# COUNTER.net
KiCad netlist of a schematic drawn in EAGLE
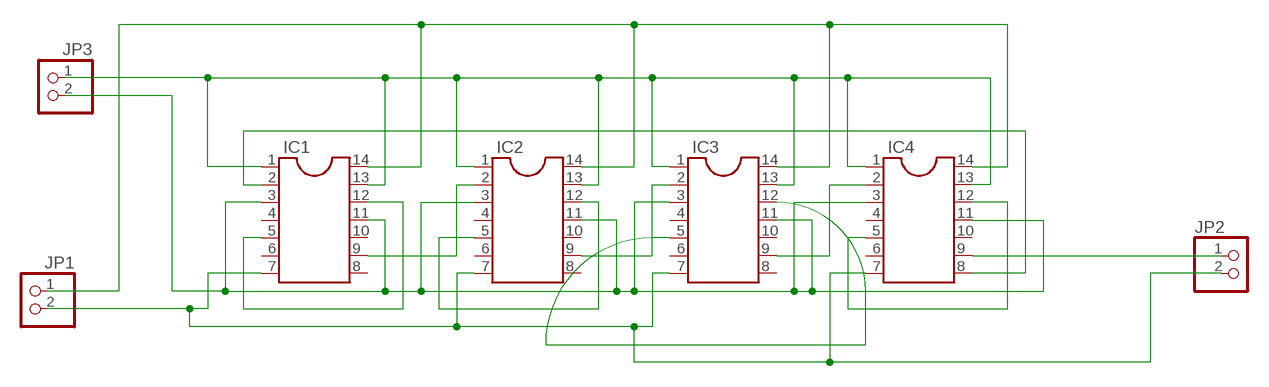
[diagram p0: schematic, sheet 1]

(export (version "E")
  (design (tool "Eeschema 10.0.6"))
  (components
    (comp (ref "IC1")
      (value "DIL14")
      (footprint "eagle-import:DIL14")
      (libsource (lib "eagle-import") (part "DIL14"))
    )
    (comp (ref "IC2")
      (value "DIL14")
      (footprint "eagle-import:DIL14")
      (libsource (lib "eagle-import") (part "DIL14"))
    )
    (comp (ref "IC3")
      (value "DIL14")
      (footprint "eagle-import:DIL14")
      (libsource (lib "eagle-import") (part "DIL14"))
    )
    (comp (ref "IC4")
      (value "DIL14")
      (footprint "eagle-import:DIL14")
      (libsource (lib "eagle-import") (part "DIL14"))
    )
    (comp (ref "JP1")
      (value "PINHD-1X2")
      (footprint "eagle-import:1X02")
      (libsource (lib "eagle-import") (part "PINHD-1X2"))
    )
    (comp (ref "JP2")
      (value "PINHD-1X2")
      (footprint "eagle-import:1X02")
      (libsource (lib "eagle-import") (part "PINHD-1X2"))
    )
    (comp (ref "JP3")
      (value "PINHD-1X2")
      (footprint "eagle-import:1X02")
      (libsource (lib "eagle-import") (part "PINHD-1X2"))
    )
  )
  (nets
    (net (code "1") (name "Net-(IC1-Pad1)") (class "Default")
      (node (ref "IC1") (pin "1") (pinfunction "1_1") (pintype "passive"))
      (node (ref "IC1") (pin "13") (pinfunction "13_13") (pintype "passive"))
      (node (ref "IC2") (pin "1") (pinfunction "1_1") (pintype "passive"))
      (node (ref "IC2") (pin "13") (pinfunction "13_13") (pintype "passive"))
      (node (ref "IC3") (pin "1") (pinfunction "1_1") (pintype "passive"))
      (node (ref "IC3") (pin "13") (pinfunction "13_13") (pintype "passive"))
      (node (ref "IC4") (pin "1") (pinfunction "1_1") (pintype "passive"))
      (node (ref "IC4") (pin "13") (pinfunction "13_13") (pintype "passive"))
      (node (ref "JP3") (pin "1") (pinfunction "1_1") (pintype "passive"))
    )
    (net (code "2") (name "Net-(IC1-Pad2)") (class "Default")
      (node (ref "IC1") (pin "2") (pinfunction "2_2") (pintype "passive"))
      (node (ref "IC4") (pin "8") (pinfunction "8_8") (pintype "passive"))
    )
    (net (code "3") (name "Net-(IC1-Pad7)") (class "Default")
      (node (ref "IC1") (pin "7") (pinfunction "7_7") (pintype "passive"))
      (node (ref "IC2") (pin "7") (pinfunction "7_7") (pintype "passive"))
      (node (ref "IC3") (pin "7") (pinfunction "7_7") (pintype "passive"))
      (node (ref "IC4") (pin "7") (pinfunction "7_7") (pintype "passive"))
      (node (ref "JP1") (pin "2") (pinfunction "2_2") (pintype "passive"))
      (node (ref "JP2") (pin "2") (pinfunction "2_2") (pintype "passive"))
    )
    (net (code "4") (name "Net-(IC1-Pad9)") (class "Default")
      (node (ref "IC1") (pin "9") (pinfunction "9_9") (pintype "passive"))
      (node (ref "IC2") (pin "2") (pinfunction "2_2") (pintype "passive"))
    )
    (net (code "5") (name "Net-(IC1-Pad11)") (class "Default")
      (node (ref "IC1") (pin "11") (pinfunction "11_11") (pintype "passive"))
      (node (ref "IC1") (pin "3") (pinfunction "3_3") (pintype "passive"))
      (node (ref "IC2") (pin "11") (pinfunction "11_11") (pintype "passive"))
      (node (ref "IC2") (pin "3") (pinfunction "3_3") (pintype "passive"))
      (node (ref "IC3") (pin "11") (pinfunction "11_11") (pintype "passive"))
      (node (ref "IC3") (pin "3") (pinfunction "3_3") (pintype "passive"))
      (node (ref "IC4") (pin "11") (pinfunction "11_11") (pintype "passive"))
      (node (ref "IC4") (pin "3") (pinfunction "3_3") (pintype "passive"))
      (node (ref "JP3") (pin "2") (pinfunction "2_2") (pintype "passive"))
    )
    (net (code "6") (name "Net-(IC1-Pad12)") (class "Default")
      (node (ref "IC1") (pin "12") (pinfunction "12_12") (pintype "passive"))
      (node (ref "IC1") (pin "5") (pinfunction "5_5") (pintype "passive"))
    )
    (net (code "7") (name "Net-(IC1-Pad14)") (class "Default")
      (node (ref "IC1") (pin "14") (pinfunction "14_14") (pintype "passive"))
      (node (ref "IC2") (pin "14") (pinfunction "14_14") (pintype "passive"))
      (node (ref "IC3") (pin "14") (pinfunction "14_14") (pintype "passive"))
      (node (ref "IC4") (pin "14") (pinfunction "14_14") (pintype "passive"))
      (node (ref "JP1") (pin "1") (pinfunction "1_1") (pintype "passive"))
    )
    (net (code "8") (name "Net-(IC2-Pad9)") (class "Default")
      (node (ref "IC2") (pin "9") (pinfunction "9_9") (pintype "passive"))
      (node (ref "IC3") (pin "2") (pinfunction "2_2") (pintype "passive"))
    )
    (net (code "9") (name "Net-(IC2-Pad12)") (class "Default")
      (node (ref "IC2") (pin "12") (pinfunction "12_12") (pintype "passive"))
      (node (ref "IC2") (pin "5") (pinfunction "5_5") (pintype "passive"))
    )
    (net (code "10") (name "Net-(IC3-Pad9)") (class "Default")
      (node (ref "IC3") (pin "9") (pinfunction "9_9") (pintype "passive"))
      (node (ref "IC4") (pin "2") (pinfunction "2_2") (pintype "passive"))
    )
    (net (code "11") (name "Net-(IC3-Pad12)") (class "Default")
      (node (ref "IC3") (pin "12") (pinfunction "12_12") (pintype "passive"))
      (node (ref "IC3") (pin "5") (pinfunction "5_5") (pintype "passive"))
    )
    (net (code "12") (name "Net-(IC4-Pad9)") (class "Default")
      (node (ref "IC4") (pin "9") (pinfunction "9_9") (pintype "passive"))
      (node (ref "JP2") (pin "1") (pinfunction "1_1") (pintype "passive"))
    )
    (net (code "13") (name "Net-(IC4-Pad12)") (class "Default")
      (node (ref "IC4") (pin "12") (pinfunction "12_12") (pintype "passive"))
      (node (ref "IC4") (pin "5") (pinfunction "5_5") (pintype "passive"))
    )
    (net (code "14") (name "unconnected-(IC1-Pad4)") (class "Default")
      (node (ref "IC1") (pin "4") (pinfunction "4_4") (pintype "passive"))
    )
    (net (code "15") (name "unconnected-(IC1-Pad6)") (class "Default")
      (node (ref "IC1") (pin "6") (pinfunction "6_6") (pintype "passive"))
    )
    (net (code "16") (name "unconnected-(IC1-Pad8)") (class "Default")
      (node (ref "IC1") (pin "8") (pinfunction "8_8") (pintype "passive"))
    )
    (net (code "17") (name "unconnected-(IC1-Pad10)") (class "Default")
      (node (ref "IC1") (pin "10") (pinfunction "10_10") (pintype "passive"))
    )
    (net (code "18") (name "unconnected-(IC2-Pad4)") (class "Default")
      (node (ref "IC2") (pin "4") (pinfunction "4_4") (pintype "passive"))
    )
    (net (code "19") (name "unconnected-(IC2-Pad6)") (class "Default")
      (node (ref "IC2") (pin "6") (pinfunction "6_6") (pintype "passive"))
    )
    (net (code "20") (name "unconnected-(IC2-Pad8)") (class "Default")
      (node (ref "IC2") (pin "8") (pinfunction "8_8") (pintype "passive"))
    )
    (net (code "21") (name "unconnected-(IC2-Pad10)") (class "Default")
      (node (ref "IC2") (pin "10") (pinfunction "10_10") (pintype "passive"))
    )
    (net (code "22") (name "unconnected-(IC3-Pad4)") (class "Default")
      (node (ref "IC3") (pin "4") (pinfunction "4_4") (pintype "passive"))
    )
    (net (code "23") (name "unconnected-(IC3-Pad6)") (class "Default")
      (node (ref "IC3") (pin "6") (pinfunction "6_6") (pintype "passive"))
    )
    (net (code "24") (name "unconnected-(IC3-Pad8)") (class "Default")
      (node (ref "IC3") (pin "8") (pinfunction "8_8") (pintype "passive"))
    )
    (net (code "25") (name "unconnected-(IC3-Pad10)") (class "Default")
      (node (ref "IC3") (pin "10") (pinfunction "10_10") (pintype "passive"))
    )
    (net (code "26") (name "unconnected-(IC4-Pad4)") (class "Default")
      (node (ref "IC4") (pin "4") (pinfunction "4_4") (pintype "passive"))
    )
    (net (code "27") (name "unconnected-(IC4-Pad6)") (class "Default")
      (node (ref "IC4") (pin "6") (pinfunction "6_6") (pintype "passive"))
    )
    (net (code "28") (name "unconnected-(IC4-Pad10)") (class "Default")
      (node (ref "IC4") (pin "10") (pinfunction "10_10") (pintype "passive"))
    )
  )
)
